# Hack_Final.net
KiCad netlist of a schematic drawn in Altium Designer
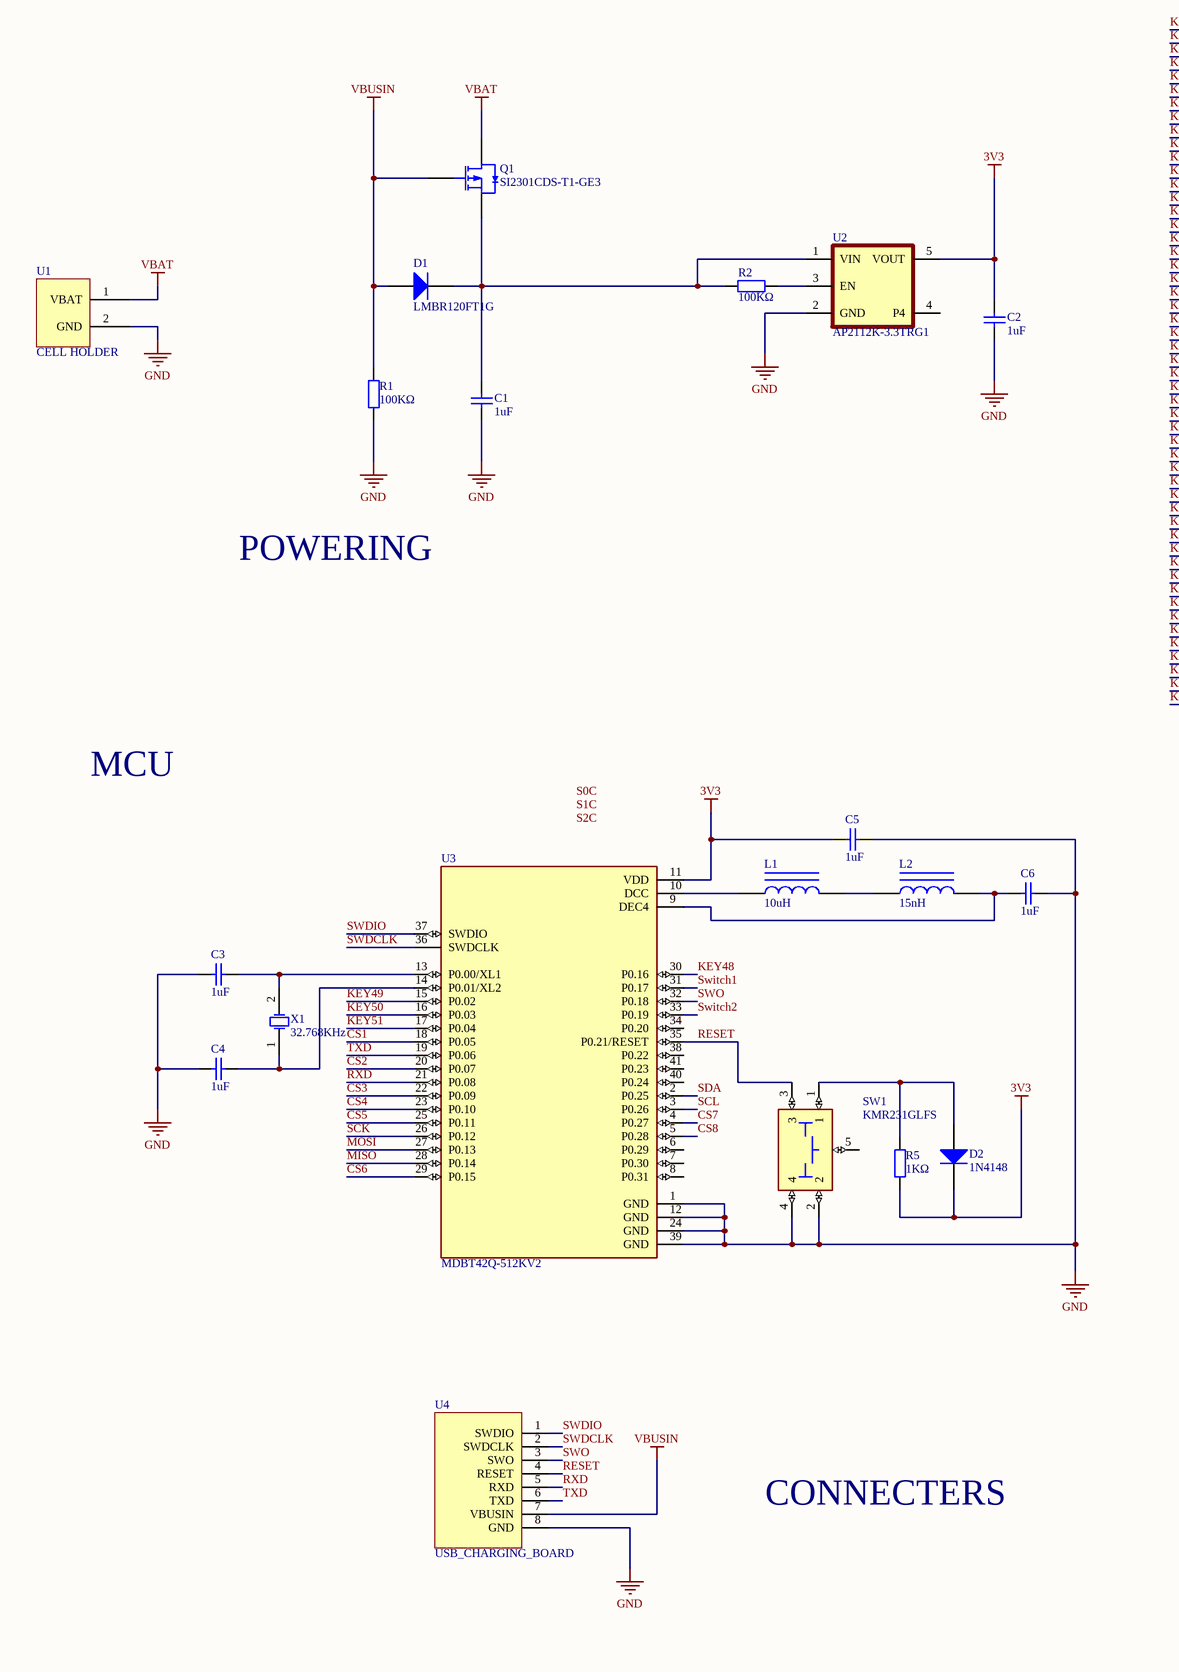
[diagram p0: Hack_Final.SchDoc, left]
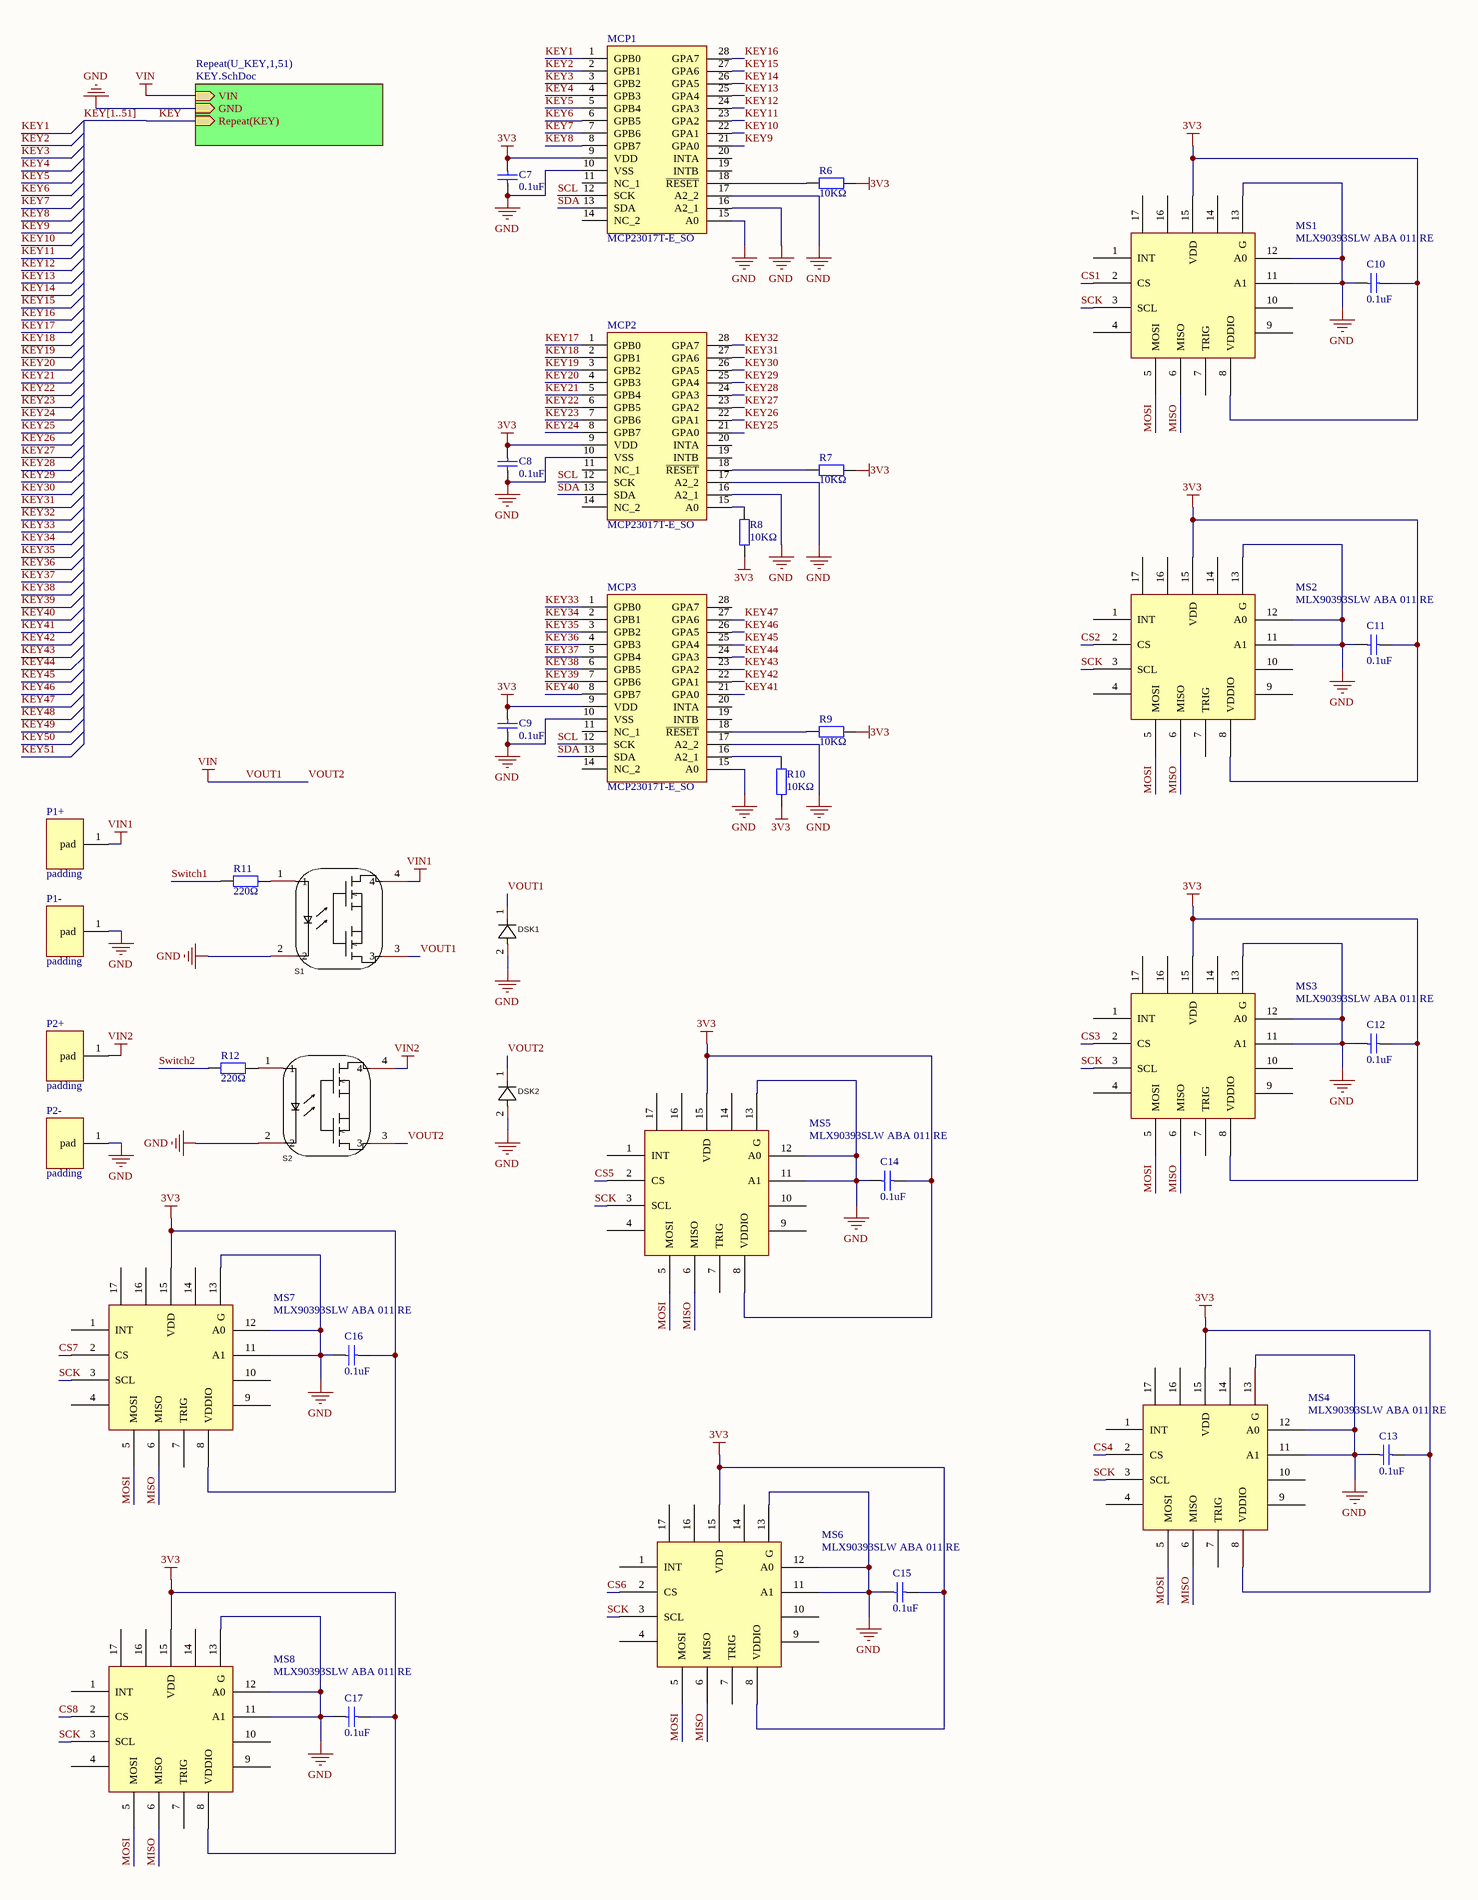
[diagram p1: Hack_Final.SchDoc, right]

(export (version "E")
  (design (tool "Eeschema 10.0.6"))
  (components
    (comp (ref "C1")
      (value "1uF")
      (footprint "0603_C")
      (description "capacitance")
      (libsource (lib "Hack_V6") (part "CAP"))
    )
    (comp (ref "C2")
      (value "1uF")
      (footprint "0603_C")
      (description "capacitance")
      (libsource (lib "Hack_V6") (part "CAP"))
    )
    (comp (ref "C3")
      (value "1uF")
      (footprint "0603_C")
      (description "capacitance")
      (libsource (lib "Hack_V6") (part "CAP"))
    )
    (comp (ref "C4")
      (value "1uF")
      (footprint "0603_C")
      (description "capacitance")
      (libsource (lib "Hack_V6") (part "CAP"))
    )
    (comp (ref "C5")
      (value "1uF")
      (footprint "0603_C")
      (description "capacitance")
      (libsource (lib "Hack_V6") (part "CAP"))
    )
    (comp (ref "C6")
      (value "1uF")
      (footprint "0603_C")
      (description "capacitance")
      (libsource (lib "Hack_V6") (part "CAP"))
    )
    (comp (ref "C7")
      (value "0.1uF")
      (footprint "0603_C")
      (description "capacitance")
      (libsource (lib "Hack_V6") (part "CAP"))
    )
    (comp (ref "C8")
      (value "0.1uF")
      (footprint "0603_C")
      (description "capacitance")
      (libsource (lib "Hack_V6") (part "CAP"))
    )
    (comp (ref "C9")
      (value "0.1uF")
      (footprint "0603_C")
      (description "capacitance")
      (libsource (lib "Hack_V6") (part "CAP"))
    )
    (comp (ref "C10")
      (value "0.1uF")
      (footprint "0603_C")
      (description "capacitance")
      (libsource (lib "Hack_V6") (part "CAP"))
    )
    (comp (ref "C11")
      (value "0.1uF")
      (footprint "0603_C")
      (description "capacitance")
      (libsource (lib "Hack_V6") (part "CAP"))
    )
    (comp (ref "C12")
      (value "0.1uF")
      (footprint "0603_C")
      (description "capacitance")
      (libsource (lib "Hack_V6") (part "CAP"))
    )
    (comp (ref "C13")
      (value "0.1uF")
      (footprint "0603_C")
      (description "capacitance")
      (libsource (lib "Hack_V6") (part "CAP"))
    )
    (comp (ref "C14")
      (value "0.1uF")
      (footprint "0603_C")
      (description "capacitance")
      (libsource (lib "Hack_V6") (part "CAP"))
    )
    (comp (ref "C15")
      (value "0.1uF")
      (footprint "0603_C")
      (description "capacitance")
      (libsource (lib "Hack_V6") (part "CAP"))
    )
    (comp (ref "C16")
      (value "0.1uF")
      (footprint "0603_C")
      (description "capacitance")
      (libsource (lib "Hack_V6") (part "CAP"))
    )
    (comp (ref "C17")
      (value "0.1uF")
      (footprint "0603_C")
      (description "capacitance")
      (libsource (lib "Hack_V6") (part "CAP"))
    )
    (comp (ref "D1")
      (value "LMBR120FT1G")
      (footprint "SOD-123")
      (description "schottky diode")
      (libsource (lib "Hack_V6") (part "DIO_5"))
    )
    (comp (ref "D2")
      (value "1N4148")
      (footprint "SOD-323F")
      (description "diode")
      (libsource (lib "MAGNETO") (part "DIO_4"))
    )
    (comp (ref "DSK1")
      (value "DSK16")
      (footprint "DSK16")
      (fields (field (name "MANUFACTURER") "HXY MOSFET(华轩阳电子)"))
      (libsource (lib "Hack_V4") (part "DSK16"))
    )
    (comp (ref "DSK2")
      (value "DSK16")
      (footprint "DSK16")
      (fields (field (name "MANUFACTURER") "HXY MOSFET(华轩阳电子)"))
      (libsource (lib "Hack_V4") (part "DSK16"))
    )
    (comp (ref "L1")
      (value "10uH")
      (footprint "0402_L")
      (description "inductance")
      (libsource (lib "magjoint_MCU") (part "IND_10uH"))
    )
    (comp (ref "L2")
      (value "15nH")
      (footprint "0402_L")
      (description "inductance")
      (libsource (lib "magjoint_MCU") (part "IND_15nH"))
    )
    (comp (ref "MCP1")
      (value "MCP23017T-E_SO")
      (footprint "SamacSys:SOIC127P1030X265-28N")
      (description "Integrated Circuit")
      (fields
        (field (name "MANUFACTURER_PART_NUMBER") "MCP23017T-E/SO")
        (field (name "MOUSER PART NUMBER") "579-MCP23017T-E/SO")
      )
      (libsource (lib "*") (part "MCP23017T-E_SO"))
    )
    (comp (ref "MCP2")
      (value "MCP23017T-E_SO")
      (footprint "SamacSys:SOIC127P1030X265-28N")
      (description "Integrated Circuit")
      (fields
        (field (name "MANUFACTURER_PART_NUMBER") "MCP23017T-E/SO")
        (field (name "MOUSER PART NUMBER") "579-MCP23017T-E/SO")
      )
      (libsource (lib "*") (part "MCP23017T-E_SO"))
    )
    (comp (ref "MCP3")
      (value "MCP23017T-E_SO")
      (footprint "SamacSys:SOIC127P1030X265-28N")
      (description "Integrated Circuit")
      (fields
        (field (name "MANUFACTURER_PART_NUMBER") "MCP23017T-E/SO")
        (field (name "MOUSER PART NUMBER") "579-MCP23017T-E/SO")
      )
      (libsource (lib "*") (part "MCP23017T-E_SO"))
    )
    (comp (ref "MS1")
      (value "MLX90393SLW ABA 011 RE")
      (footprint "VQFN-16_EP_3.0x3.0xo.5P")
      (description "sensor")
      (libsource (lib "magjoint_MCU") (part "MLX90393SLW ABA 011 RE"))
    )
    (comp (ref "MS2")
      (value "MLX90393SLW ABA 011 RE")
      (footprint "VQFN-16_EP_3.0x3.0xo.5P")
      (description "sensor")
      (libsource (lib "magjoint_MCU") (part "MLX90393SLW ABA 011 RE"))
    )
    (comp (ref "MS3")
      (value "MLX90393SLW ABA 011 RE")
      (footprint "VQFN-16_EP_3.0x3.0xo.5P")
      (description "sensor")
      (libsource (lib "magjoint_MCU") (part "MLX90393SLW ABA 011 RE"))
    )
    (comp (ref "MS4")
      (value "MLX90393SLW ABA 011 RE")
      (footprint "VQFN-16_EP_3.0x3.0xo.5P")
      (description "sensor")
      (libsource (lib "magjoint_MCU") (part "MLX90393SLW ABA 011 RE"))
    )
    (comp (ref "MS5")
      (value "MLX90393SLW ABA 011 RE")
      (footprint "VQFN-16_EP_3.0x3.0xo.5P")
      (description "sensor")
      (libsource (lib "magjoint_MCU") (part "MLX90393SLW ABA 011 RE"))
    )
    (comp (ref "MS6")
      (value "MLX90393SLW ABA 011 RE")
      (footprint "VQFN-16_EP_3.0x3.0xo.5P")
      (description "sensor")
      (libsource (lib "magjoint_MCU") (part "MLX90393SLW ABA 011 RE"))
    )
    (comp (ref "MS7")
      (value "MLX90393SLW ABA 011 RE")
      (footprint "VQFN-16_EP_3.0x3.0xo.5P")
      (description "sensor")
      (libsource (lib "magjoint_MCU") (part "MLX90393SLW ABA 011 RE"))
    )
    (comp (ref "MS8")
      (value "MLX90393SLW ABA 011 RE")
      (footprint "VQFN-16_EP_3.0x3.0xo.5P")
      (description "sensor")
      (libsource (lib "magjoint_MCU") (part "MLX90393SLW ABA 011 RE"))
    )
    (comp (ref "P1+") (value "padding") (footprint "PADDING2") (libsource (lib "Hack_V4") (part "padding2")))
    (comp (ref "P1-") (value "padding") (footprint "PADDING2") (libsource (lib "Hack_V4") (part "padding2")))
    (comp (ref "P2+") (value "padding") (footprint "PADDING2") (libsource (lib "Hack_V4") (part "padding2")))
    (comp (ref "P2-") (value "padding") (footprint "PADDING2") (libsource (lib "Hack_V4") (part "padding2")))
    (comp (ref "Q1")
      (value "SI2301CDS-T1-GE3")
      (footprint "SOT-23(SOT-23-3)")
      (description "field effect tube")
      (libsource (lib "magjoint_MCU") (part "MOS"))
    )
    (comp (ref "R1")
      (value "100KΩ")
      (footprint "0603_R")
      (description "resistance")
      (libsource (lib "") (part "RES_3"))
    )
    (comp (ref "R2")
      (value "100KΩ")
      (footprint "0603_R")
      (description "resistance")
      (libsource (lib "Hack_V6") (part "RES"))
    )
    (comp (ref "R5")
      (value "1KΩ")
      (footprint "0603_R")
      (description "resistance")
      (libsource (lib "") (part "RES_2"))
    )
    (comp (ref "R6")
      (value "10KΩ")
      (footprint "0603_R")
      (description "resistance")
      (libsource (lib "Hack_V6") (part "RES"))
    )
    (comp (ref "R7")
      (value "10KΩ")
      (footprint "0603_R")
      (description "resistance")
      (libsource (lib "Hack_V6") (part "RES"))
    )
    (comp (ref "R8")
      (value "10KΩ")
      (footprint "0603_R")
      (description "resistance")
      (libsource (lib "") (part "RES_2"))
    )
    (comp (ref "R9")
      (value "10KΩ")
      (footprint "0603_R")
      (description "resistance")
      (libsource (lib "Hack_V6") (part "RES"))
    )
    (comp (ref "R10")
      (value "10KΩ")
      (footprint "0603_R")
      (description "resistance")
      (libsource (lib "") (part "RES_2"))
    )
    (comp (ref "R11")
      (value "220Ω")
      (footprint "0603_R")
      (description "resistance")
      (libsource (lib "") (part "RES_1"))
    )
    (comp (ref "R12")
      (value "220Ω")
      (footprint "0603_R")
      (description "resistance")
      (libsource (lib "") (part "RES_1"))
    )
    (comp (ref "S1")
      (value "GAQY212GSX")
      (footprint "SOP-4_L4.3-W4.4-P2.54-LS6.8-TR")
      (fields (field (name "MANUFACTURER") "SUPSiC(国晶微半导体)"))
      (libsource (lib "Hack_V3") (part "GAQY212GSX"))
    )
    (comp (ref "S2")
      (value "GAQY212GSX")
      (footprint "SOP-4_L4.3-W4.4-P2.54-LS6.8-TR")
      (fields (field (name "MANUFACTURER") "SUPSiC(国晶微半导体)"))
      (libsource (lib "Hack_V3") (part "GAQY212GSX"))
    )
    (comp (ref "SW1")
      (value "KMR231GLFS")
      (footprint "KMR231GLFS")
      (description "Tactile Switch SPST-NO Top Actuated Surface Mount")
      (libsource (lib "magjoint_MCU") (part "KMR231GLFS"))
    )
    (comp (ref "U1")
      (value "CELL HOLDER")
      (footprint "BAT_MX 1.25-WI-2P")
      (description "button cell battary holder BS-08-B2AA025")
      (libsource (lib "magjoint_MCU") (part "BAT"))
    )
    (comp (ref "U2")
      (value "AP2112K-3.3TRG1")
      (footprint "SOT95P285X140-5N")
      (description "LDO_ low dropout linear regulator")
      (libsource (lib "magjoint_MCU") (part "AP2112K"))
    )
    (comp (ref "U3")
      (value "MDBT42Q-512KV2")
      (footprint "SMD_10.0X16.0")
      (libsource (lib "magjoint_MCU") (part "MDBT42Q-512KV2"))
    )
    (comp (ref "U4")
      (value "USB_CHARGING_BOARD")
      (footprint "FPC0.5 2H-WS-8P")
      (libsource (lib "magjoint_MCU") (part "USB_CHARGING_BOARD"))
    )
    (comp (ref "X1")
      (value "32.768KHz")
      (footprint "SMD-3215_2P FC - 135")
      (description "crystal")
      (libsource (lib "magjoint_MCU") (part "ABS07-32.768KHZ-7-T"))
    )
  )
  (nets
    (net (code "1") (name "/CS1") (class "Default")
      (node (ref "MS1") (pin "2") (pinfunction "CS_2") (pintype "passive"))
      (node (ref "U3") (pin "18") (pinfunction "P0.05_18") (pintype "bidirectional"))
    )
    (net (code "2") (name "/CS2") (class "Default")
      (node (ref "MS2") (pin "2") (pinfunction "CS_2") (pintype "passive"))
      (node (ref "U3") (pin "20") (pinfunction "P0.07_20") (pintype "bidirectional"))
    )
    (net (code "3") (name "/CS3") (class "Default")
      (node (ref "MS3") (pin "2") (pinfunction "CS_2") (pintype "passive"))
      (node (ref "U3") (pin "22") (pinfunction "P0.09_22") (pintype "bidirectional"))
    )
    (net (code "4") (name "/CS4") (class "Default")
      (node (ref "MS4") (pin "2") (pinfunction "CS_2") (pintype "passive"))
      (node (ref "U3") (pin "23") (pinfunction "P0.10_23") (pintype "bidirectional"))
    )
    (net (code "5") (name "/CS5") (class "Default")
      (node (ref "MS5") (pin "2") (pinfunction "CS_2") (pintype "passive"))
      (node (ref "U3") (pin "25") (pinfunction "P0.11_25") (pintype "bidirectional"))
    )
    (net (code "6") (name "/CS6") (class "Default")
      (node (ref "MS6") (pin "2") (pinfunction "CS_2") (pintype "passive"))
      (node (ref "U3") (pin "29") (pinfunction "P0.15_29") (pintype "bidirectional"))
    )
    (net (code "7") (name "/CS7") (class "Default")
      (node (ref "MS7") (pin "2") (pinfunction "CS_2") (pintype "passive"))
      (node (ref "U3") (pin "4") (pinfunction "P0.27_4") (pintype "bidirectional"))
    )
    (net (code "8") (name "/CS8") (class "Default")
      (node (ref "MS8") (pin "2") (pinfunction "CS_2") (pintype "passive"))
      (node (ref "U3") (pin "5") (pinfunction "P0.28_5") (pintype "bidirectional"))
    )
    (net (code "10") (name "/KEY1") (class "Default")
      (node (ref "MCP1") (pin "1") (pinfunction "GPB0_1") (pintype "passive"))
    )
    (net (code "11") (name "/KEY2") (class "Default")
      (node (ref "MCP1") (pin "2") (pinfunction "GPB1_2") (pintype "passive"))
    )
    (net (code "12") (name "/KEY3") (class "Default")
      (node (ref "MCP1") (pin "3") (pinfunction "GPB2_3") (pintype "passive"))
    )
    (net (code "13") (name "/KEY4") (class "Default")
      (node (ref "MCP1") (pin "4") (pinfunction "GPB3_4") (pintype "passive"))
    )
    (net (code "14") (name "/KEY5") (class "Default")
      (node (ref "MCP1") (pin "5") (pinfunction "GPB4_5") (pintype "passive"))
    )
    (net (code "15") (name "/KEY6") (class "Default")
      (node (ref "MCP1") (pin "6") (pinfunction "GPB5_6") (pintype "passive"))
    )
    (net (code "16") (name "/KEY7") (class "Default")
      (node (ref "MCP1") (pin "7") (pinfunction "GPB6_7") (pintype "passive"))
    )
    (net (code "17") (name "/KEY8") (class "Default")
      (node (ref "MCP1") (pin "8") (pinfunction "GPB7_8") (pintype "passive"))
    )
    (net (code "18") (name "/KEY9") (class "Default")
      (node (ref "MCP1") (pin "21") (pinfunction "GPA0_21") (pintype "passive"))
    )
    (net (code "19") (name "/KEY10") (class "Default")
      (node (ref "MCP1") (pin "22") (pinfunction "GPA1_22") (pintype "passive"))
    )
    (net (code "20") (name "/KEY11") (class "Default")
      (node (ref "MCP1") (pin "23") (pinfunction "GPA2_23") (pintype "passive"))
    )
    (net (code "21") (name "/KEY12") (class "Default")
      (node (ref "MCP1") (pin "24") (pinfunction "GPA3_24") (pintype "passive"))
    )
    (net (code "22") (name "/KEY13") (class "Default")
      (node (ref "MCP1") (pin "25") (pinfunction "GPA4_25") (pintype "passive"))
    )
    (net (code "23") (name "/KEY14") (class "Default")
      (node (ref "MCP1") (pin "26") (pinfunction "GPA5_26") (pintype "passive"))
    )
    (net (code "24") (name "/KEY15") (class "Default")
      (node (ref "MCP1") (pin "27") (pinfunction "GPA6_27") (pintype "passive"))
    )
    (net (code "25") (name "/KEY16") (class "Default")
      (node (ref "MCP1") (pin "28") (pinfunction "GPA7_28") (pintype "passive"))
    )
    (net (code "26") (name "/KEY17") (class "Default")
      (node (ref "MCP2") (pin "1") (pinfunction "GPB0_1") (pintype "passive"))
    )
    (net (code "27") (name "/KEY18") (class "Default")
      (node (ref "MCP2") (pin "2") (pinfunction "GPB1_2") (pintype "passive"))
    )
    (net (code "28") (name "/KEY19") (class "Default")
      (node (ref "MCP2") (pin "3") (pinfunction "GPB2_3") (pintype "passive"))
    )
    (net (code "29") (name "/KEY20") (class "Default")
      (node (ref "MCP2") (pin "4") (pinfunction "GPB3_4") (pintype "passive"))
    )
    (net (code "30") (name "/KEY21") (class "Default")
      (node (ref "MCP2") (pin "5") (pinfunction "GPB4_5") (pintype "passive"))
    )
    (net (code "31") (name "/KEY22") (class "Default")
      (node (ref "MCP2") (pin "6") (pinfunction "GPB5_6") (pintype "passive"))
    )
    (net (code "32") (name "/KEY23") (class "Default")
      (node (ref "MCP2") (pin "7") (pinfunction "GPB6_7") (pintype "passive"))
    )
    (net (code "33") (name "/KEY24") (class "Default")
      (node (ref "MCP2") (pin "8") (pinfunction "GPB7_8") (pintype "passive"))
    )
    (net (code "34") (name "/KEY25") (class "Default")
      (node (ref "MCP2") (pin "21") (pinfunction "GPA0_21") (pintype "passive"))
    )
    (net (code "35") (name "/KEY26") (class "Default")
      (node (ref "MCP2") (pin "22") (pinfunction "GPA1_22") (pintype "passive"))
    )
    (net (code "36") (name "/KEY27") (class "Default")
      (node (ref "MCP2") (pin "23") (pinfunction "GPA2_23") (pintype "passive"))
    )
    (net (code "37") (name "/KEY28") (class "Default")
      (node (ref "MCP2") (pin "24") (pinfunction "GPA3_24") (pintype "passive"))
    )
    (net (code "38") (name "/KEY29") (class "Default")
      (node (ref "MCP2") (pin "25") (pinfunction "GPA4_25") (pintype "passive"))
    )
    (net (code "39") (name "/KEY30") (class "Default")
      (node (ref "MCP2") (pin "26") (pinfunction "GPA5_26") (pintype "passive"))
    )
    (net (code "40") (name "/KEY31") (class "Default")
      (node (ref "MCP2") (pin "27") (pinfunction "GPA6_27") (pintype "passive"))
    )
    (net (code "41") (name "/KEY32") (class "Default")
      (node (ref "MCP2") (pin "28") (pinfunction "GPA7_28") (pintype "passive"))
    )
    (net (code "42") (name "/KEY33") (class "Default")
      (node (ref "MCP3") (pin "1") (pinfunction "GPB0_1") (pintype "passive"))
    )
    (net (code "43") (name "/KEY34") (class "Default")
      (node (ref "MCP3") (pin "2") (pinfunction "GPB1_2") (pintype "passive"))
    )
    (net (code "44") (name "/KEY35") (class "Default")
      (node (ref "MCP3") (pin "3") (pinfunction "GPB2_3") (pintype "passive"))
    )
    (net (code "45") (name "/KEY36") (class "Default")
      (node (ref "MCP3") (pin "4") (pinfunction "GPB3_4") (pintype "passive"))
    )
    (net (code "46") (name "/KEY37") (class "Default")
      (node (ref "MCP3") (pin "5") (pinfunction "GPB4_5") (pintype "passive"))
    )
    (net (code "47") (name "/KEY38") (class "Default")
      (node (ref "MCP3") (pin "6") (pinfunction "GPB5_6") (pintype "passive"))
    )
    (net (code "48") (name "/KEY39") (class "Default")
      (node (ref "MCP3") (pin "7") (pinfunction "GPB6_7") (pintype "passive"))
    )
    (net (code "49") (name "/KEY40") (class "Default")
      (node (ref "MCP3") (pin "8") (pinfunction "GPB7_8") (pintype "passive"))
    )
    (net (code "50") (name "/KEY41") (class "Default")
      (node (ref "MCP3") (pin "21") (pinfunction "GPA0_21") (pintype "passive"))
    )
    (net (code "51") (name "/KEY42") (class "Default")
      (node (ref "MCP3") (pin "22") (pinfunction "GPA1_22") (pintype "passive"))
    )
    (net (code "52") (name "/KEY43") (class "Default")
      (node (ref "MCP3") (pin "23") (pinfunction "GPA2_23") (pintype "passive"))
    )
    (net (code "53") (name "/KEY44") (class "Default")
      (node (ref "MCP3") (pin "24") (pinfunction "GPA3_24") (pintype "passive"))
    )
    (net (code "54") (name "/KEY45") (class "Default")
      (node (ref "MCP3") (pin "25") (pinfunction "GPA4_25") (pintype "passive"))
    )
    (net (code "55") (name "/KEY46") (class "Default")
      (node (ref "MCP3") (pin "26") (pinfunction "GPA5_26") (pintype "passive"))
    )
    (net (code "56") (name "/KEY47") (class "Default")
      (node (ref "MCP3") (pin "27") (pinfunction "GPA6_27") (pintype "passive"))
    )
    (net (code "57") (name "/KEY48") (class "Default")
      (node (ref "U3") (pin "30") (pinfunction "P0.16_30") (pintype "bidirectional"))
    )
    (net (code "58") (name "/KEY49") (class "Default")
      (node (ref "U3") (pin "15") (pinfunction "P0.02_15") (pintype "bidirectional"))
    )
    (net (code "59") (name "/KEY50") (class "Default")
      (node (ref "U3") (pin "16") (pinfunction "P0.03_16") (pintype "bidirectional"))
    )
    (net (code "60") (name "/KEY51") (class "Default")
      (node (ref "U3") (pin "17") (pinfunction "P0.04_17") (pintype "bidirectional"))
    )
    (net (code "62") (name "/MISO") (class "Default")
      (node (ref "MS1") (pin "6") (pinfunction "MISO_6") (pintype "passive"))
      (node (ref "MS2") (pin "6") (pinfunction "MISO_6") (pintype "passive"))
      (node (ref "MS3") (pin "6") (pinfunction "MISO_6") (pintype "passive"))
      (node (ref "MS4") (pin "6") (pinfunction "MISO_6") (pintype "passive"))
      (node (ref "MS5") (pin "6") (pinfunction "MISO_6") (pintype "passive"))
      (node (ref "MS6") (pin "6") (pinfunction "MISO_6") (pintype "passive"))
      (node (ref "MS7") (pin "6") (pinfunction "MISO_6") (pintype "passive"))
      (node (ref "MS8") (pin "6") (pinfunction "MISO_6") (pintype "passive"))
      (node (ref "U3") (pin "28") (pinfunction "P0.14_28") (pintype "bidirectional"))
    )
    (net (code "63") (name "/MOSI") (class "Default")
      (node (ref "MS1") (pin "5") (pinfunction "MOSI_5") (pintype "passive"))
      (node (ref "MS2") (pin "5") (pinfunction "MOSI_5") (pintype "passive"))
      (node (ref "MS3") (pin "5") (pinfunction "MOSI_5") (pintype "passive"))
      (node (ref "MS4") (pin "5") (pinfunction "MOSI_5") (pintype "passive"))
      (node (ref "MS5") (pin "5") (pinfunction "MOSI_5") (pintype "passive"))
      (node (ref "MS6") (pin "5") (pinfunction "MOSI_5") (pintype "passive"))
      (node (ref "MS7") (pin "5") (pinfunction "MOSI_5") (pintype "passive"))
      (node (ref "MS8") (pin "5") (pinfunction "MOSI_5") (pintype "passive"))
      (node (ref "U3") (pin "27") (pinfunction "P0.13_27") (pintype "bidirectional"))
    )
    (net (code "64") (name "/RESET") (class "Default")
      (node (ref "SW1") (pin "3") (pinfunction "3_3") (pintype "bidirectional"))
      (node (ref "U3") (pin "35") (pinfunction "P0.21/RESET_35") (pintype "bidirectional"))
      (node (ref "U4") (pin "4") (pinfunction "RESET_4") (pintype "passive"))
    )
    (net (code "65") (name "/RXD") (class "Default")
      (node (ref "U3") (pin "21") (pinfunction "P0.08_21") (pintype "bidirectional"))
      (node (ref "U4") (pin "5") (pinfunction "RXD_5") (pintype "passive"))
    )
    (net (code "69") (name "/SCK") (class "Default")
      (node (ref "MS1") (pin "3") (pinfunction "SCL_3") (pintype "passive"))
      (node (ref "MS2") (pin "3") (pinfunction "SCL_3") (pintype "passive"))
      (node (ref "MS3") (pin "3") (pinfunction "SCL_3") (pintype "passive"))
      (node (ref "MS4") (pin "3") (pinfunction "SCL_3") (pintype "passive"))
      (node (ref "MS5") (pin "3") (pinfunction "SCL_3") (pintype "passive"))
      (node (ref "MS6") (pin "3") (pinfunction "SCL_3") (pintype "passive"))
      (node (ref "MS7") (pin "3") (pinfunction "SCL_3") (pintype "passive"))
      (node (ref "MS8") (pin "3") (pinfunction "SCL_3") (pintype "passive"))
      (node (ref "U3") (pin "26") (pinfunction "P0.12_26") (pintype "bidirectional"))
    )
    (net (code "70") (name "/SCL") (class "Default")
      (node (ref "MCP1") (pin "12") (pinfunction "SCK_12") (pintype "passive"))
      (node (ref "MCP2") (pin "12") (pinfunction "SCK_12") (pintype "passive"))
      (node (ref "MCP3") (pin "12") (pinfunction "SCK_12") (pintype "passive"))
      (node (ref "U3") (pin "3") (pinfunction "P0.26_3") (pintype "bidirectional"))
    )
    (net (code "71") (name "/SDA") (class "Default")
      (node (ref "MCP1") (pin "13") (pinfunction "SDA_13") (pintype "passive"))
      (node (ref "MCP2") (pin "13") (pinfunction "SDA_13") (pintype "passive"))
      (node (ref "MCP3") (pin "13") (pinfunction "SDA_13") (pintype "passive"))
      (node (ref "U3") (pin "2") (pinfunction "P0.25_2") (pintype "bidirectional"))
    )
    (net (code "72") (name "/SWDCLK") (class "Default")
      (node (ref "U3") (pin "36") (pinfunction "SWDCLK_36") (pintype "power_in"))
      (node (ref "U4") (pin "2") (pinfunction "SWDCLK_2") (pintype "passive"))
    )
    (net (code "73") (name "/SWDIO") (class "Default")
      (node (ref "U3") (pin "37") (pinfunction "SWDIO_37") (pintype "bidirectional"))
      (node (ref "U4") (pin "1") (pinfunction "SWDIO_1") (pintype "passive"))
    )
    (net (code "74") (name "/SWO") (class "Default")
      (node (ref "U3") (pin "32") (pinfunction "P0.18_32") (pintype "bidirectional"))
      (node (ref "U4") (pin "3") (pinfunction "SWO_3") (pintype "passive"))
    )
    (net (code "75") (name "/Switch1") (class "Default")
      (node (ref "R11") (pin "1") (pinfunction "1_1") (pintype "passive"))
      (node (ref "U3") (pin "31") (pinfunction "P0.17_31") (pintype "bidirectional"))
    )
    (net (code "76") (name "/Switch2") (class "Default")
      (node (ref "R12") (pin "1") (pinfunction "1_1") (pintype "passive"))
      (node (ref "U3") (pin "33") (pinfunction "P0.19_33") (pintype "bidirectional"))
    )
    (net (code "77") (name "/TXD") (class "Default")
      (node (ref "U3") (pin "19") (pinfunction "P0.06_19") (pintype "bidirectional"))
      (node (ref "U4") (pin "6") (pinfunction "TXD_6") (pintype "passive"))
    )
    (net (code "78") (name "3V3") (class "Default")
      (node (ref "C10") (pin "2") (pinfunction "2_2") (pintype "passive"))
      (node (ref "C11") (pin "2") (pinfunction "2_2") (pintype "passive"))
      (node (ref "C12") (pin "2") (pinfunction "2_2") (pintype "passive"))
      (node (ref "C13") (pin "2") (pinfunction "2_2") (pintype "passive"))
      (node (ref "C14") (pin "2") (pinfunction "2_2") (pintype "passive"))
      (node (ref "C15") (pin "2") (pinfunction "2_2") (pintype "passive"))
      (node (ref "C16") (pin "2") (pinfunction "2_2") (pintype "passive"))
      (node (ref "C17") (pin "2") (pinfunction "2_2") (pintype "passive"))
      (node (ref "C2") (pin "2") (pinfunction "2_2") (pintype "passive"))
      (node (ref "C5") (pin "2") (pinfunction "2_2") (pintype "passive"))
      (node (ref "C7") (pin "1") (pinfunction "1_1") (pintype "passive"))
      (node (ref "C8") (pin "1") (pinfunction "1_1") (pintype "passive"))
      (node (ref "C9") (pin "1") (pinfunction "1_1") (pintype "passive"))
      (node (ref "D2") (pin "2") (pinfunction "K_2") (pintype "passive"))
      (node (ref "MCP1") (pin "9") (pinfunction "VDD_9") (pintype "passive"))
      (node (ref "MCP2") (pin "9") (pinfunction "VDD_9") (pintype "passive"))
      (node (ref "MCP3") (pin "9") (pinfunction "VDD_9") (pintype "passive"))
      (node (ref "MS1") (pin "15") (pinfunction "VDD_15") (pintype "passive"))
      (node (ref "MS1") (pin "8") (pinfunction "VDDIO_8") (pintype "passive"))
      (node (ref "MS2") (pin "15") (pinfunction "VDD_15") (pintype "passive"))
      (node (ref "MS2") (pin "8") (pinfunction "VDDIO_8") (pintype "passive"))
      (node (ref "MS3") (pin "15") (pinfunction "VDD_15") (pintype "passive"))
      (node (ref "MS3") (pin "8") (pinfunction "VDDIO_8") (pintype "passive"))
      (node (ref "MS4") (pin "15") (pinfunction "VDD_15") (pintype "passive"))
      (node (ref "MS4") (pin "8") (pinfunction "VDDIO_8") (pintype "passive"))
      (node (ref "MS5") (pin "15") (pinfunction "VDD_15") (pintype "passive"))
      (node (ref "MS5") (pin "8") (pinfunction "VDDIO_8") (pintype "passive"))
      (node (ref "MS6") (pin "15") (pinfunction "VDD_15") (pintype "passive"))
      (node (ref "MS6") (pin "8") (pinfunction "VDDIO_8") (pintype "passive"))
      (node (ref "MS7") (pin "15") (pinfunction "VDD_15") (pintype "passive"))
      (node (ref "MS7") (pin "8") (pinfunction "VDDIO_8") (pintype "passive"))
      (node (ref "MS8") (pin "15") (pinfunction "VDD_15") (pintype "passive"))
      (node (ref "MS8") (pin "8") (pinfunction "VDDIO_8") (pintype "passive"))
      (node (ref "R10") (pin "2") (pinfunction "2_2") (pintype "passive"))
      (node (ref "R5") (pin "2") (pinfunction "2_2") (pintype "passive"))
      (node (ref "R6") (pin "1") (pinfunction "1_1") (pintype "passive"))
      (node (ref "R7") (pin "1") (pinfunction "1_1") (pintype "passive"))
      (node (ref "R8") (pin "2") (pinfunction "2_2") (pintype "passive"))
      (node (ref "R9") (pin "1") (pinfunction "1_1") (pintype "passive"))
      (node (ref "U2") (pin "5") (pinfunction "VOUT_5") (pintype "power_in"))
      (node (ref "U3") (pin "11") (pinfunction "VDD_11") (pintype "power_in"))
    )
    (net (code "79") (name "GND") (class "Default")
      (node (ref "C1") (pin "1") (pinfunction "1_1") (pintype "passive"))
      (node (ref "C10") (pin "1") (pinfunction "1_1") (pintype "passive"))
      (node (ref "C11") (pin "1") (pinfunction "1_1") (pintype "passive"))
      (node (ref "C12") (pin "1") (pinfunction "1_1") (pintype "passive"))
      (node (ref "C13") (pin "1") (pinfunction "1_1") (pintype "passive"))
      (node (ref "C14") (pin "1") (pinfunction "1_1") (pintype "passive"))
      (node (ref "C15") (pin "1") (pinfunction "1_1") (pintype "passive"))
      (node (ref "C16") (pin "1") (pinfunction "1_1") (pintype "passive"))
      (node (ref "C17") (pin "1") (pinfunction "1_1") (pintype "passive"))
      (node (ref "C2") (pin "1") (pinfunction "1_1") (pintype "passive"))
      (node (ref "C3") (pin "2") (pinfunction "2_2") (pintype "passive"))
      (node (ref "C4") (pin "2") (pinfunction "2_2") (pintype "passive"))
      (node (ref "C5") (pin "1") (pinfunction "1_1") (pintype "passive"))
      (node (ref "C6") (pin "1") (pinfunction "1_1") (pintype "passive"))
      (node (ref "C7") (pin "2") (pinfunction "2_2") (pintype "passive"))
      (node (ref "C8") (pin "2") (pinfunction "2_2") (pintype "passive"))
      (node (ref "C9") (pin "2") (pinfunction "2_2") (pintype "passive"))
      (node (ref "DSK1") (pin "2") (pinfunction "A_2") (pintype "passive"))
      (node (ref "DSK2") (pin "2") (pinfunction "A_2") (pintype "passive"))
      (node (ref "MCP1") (pin "10") (pinfunction "VSS_10") (pintype "passive"))
      (node (ref "MCP1") (pin "15") (pinfunction "A0_15") (pintype "passive"))
      (node (ref "MCP1") (pin "16") (pinfunction "A2_1_16") (pintype "passive"))
      (node (ref "MCP1") (pin "17") (pinfunction "A2_2_17") (pintype "passive"))
      (node (ref "MCP2") (pin "10") (pinfunction "VSS_10") (pintype "passive"))
      (node (ref "MCP2") (pin "16") (pinfunction "A2_1_16") (pintype "passive"))
      (node (ref "MCP2") (pin "17") (pinfunction "A2_2_17") (pintype "passive"))
      (node (ref "MCP3") (pin "10") (pinfunction "VSS_10") (pintype "passive"))
      (node (ref "MCP3") (pin "15") (pinfunction "A0_15") (pintype "passive"))
      (node (ref "MCP3") (pin "17") (pinfunction "A2_2_17") (pintype "passive"))
      (node (ref "MS1") (pin "11") (pinfunction "A1_11") (pintype "passive"))
      (node (ref "MS1") (pin "12") (pinfunction "A0_12") (pintype "passive"))
      (node (ref "MS1") (pin "13") (pinfunction "G_13") (pintype "passive"))
      (node (ref "MS2") (pin "11") (pinfunction "A1_11") (pintype "passive"))
      (node (ref "MS2") (pin "12") (pinfunction "A0_12") (pintype "passive"))
      (node (ref "MS2") (pin "13") (pinfunction "G_13") (pintype "passive"))
      (node (ref "MS3") (pin "11") (pinfunction "A1_11") (pintype "passive"))
      (node (ref "MS3") (pin "12") (pinfunction "A0_12") (pintype "passive"))
      (node (ref "MS3") (pin "13") (pinfunction "G_13") (pintype "passive"))
      (node (ref "MS4") (pin "11") (pinfunction "A1_11") (pintype "passive"))
      (node (ref "MS4") (pin "12") (pinfunction "A0_12") (pintype "passive"))
      (node (ref "MS4") (pin "13") (pinfunction "G_13") (pintype "passive"))
      (node (ref "MS5") (pin "11") (pinfunction "A1_11") (pintype "passive"))
      (node (ref "MS5") (pin "12") (pinfunction "A0_12") (pintype "passive"))
      (node (ref "MS5") (pin "13") (pinfunction "G_13") (pintype "passive"))
      (node (ref "MS6") (pin "11") (pinfunction "A1_11") (pintype "passive"))
      (node (ref "MS6") (pin "12") (pinfunction "A0_12") (pintype "passive"))
      (node (ref "MS6") (pin "13") (pinfunction "G_13") (pintype "passive"))
      (node (ref "MS7") (pin "11") (pinfunction "A1_11") (pintype "passive"))
      (node (ref "MS7") (pin "12") (pinfunction "A0_12") (pintype "passive"))
      (node (ref "MS7") (pin "13") (pinfunction "G_13") (pintype "passive"))
      (node (ref "MS8") (pin "11") (pinfunction "A1_11") (pintype "passive"))
      (node (ref "MS8") (pin "12") (pinfunction "A0_12") (pintype "passive"))
      (node (ref "MS8") (pin "13") (pinfunction "G_13") (pintype "passive"))
      (node (ref "P1-") (pin "1") (pinfunction "pad_1") (pintype "passive"))
      (node (ref "P2-") (pin "1") (pinfunction "pad_1") (pintype "passive"))
      (node (ref "R1") (pin "1") (pinfunction "1_1") (pintype "passive"))
      (node (ref "S1") (pin "2") (pinfunction "2_2") (pintype "passive"))
      (node (ref "S2") (pin "2") (pinfunction "2_2") (pintype "passive"))
      (node (ref "SW1") (pin "2") (pinfunction "2_2") (pintype "bidirectional"))
      (node (ref "SW1") (pin "4") (pinfunction "4_4") (pintype "bidirectional"))
      (node (ref "U1") (pin "2") (pinfunction "GND_2") (pintype "passive"))
      (node (ref "U2") (pin "2") (pinfunction "GND_2") (pintype "power_in"))
      (node (ref "U3") (pin "1") (pinfunction "GND_1") (pintype "power_in"))
      (node (ref "U3") (pin "12") (pinfunction "GND_12") (pintype "power_in"))
      (node (ref "U3") (pin "24") (pinfunction "GND_24") (pintype "power_in"))
      (node (ref "U3") (pin "39") (pinfunction "GND_39") (pintype "power_in"))
      (node (ref "U4") (pin "8") (pinfunction "GND_8") (pintype "passive"))
    )
    (net (code "80") (name "Net-(D1-K)") (class "Default")
      (node (ref "C1") (pin "2") (pinfunction "2_2") (pintype "passive"))
      (node (ref "D1") (pin "2") (pinfunction "K_2") (pintype "passive"))
      (node (ref "Q1") (pin "2") (pinfunction "S_2") (pintype "passive"))
      (node (ref "R2") (pin "2") (pinfunction "2_2") (pintype "passive"))
      (node (ref "U2") (pin "1") (pinfunction "VIN_1") (pintype "power_in"))
    )
    (net (code "81") (name "Net-(D2-A)") (class "Default")
      (node (ref "D2") (pin "1") (pinfunction "A_1") (pintype "passive"))
      (node (ref "R5") (pin "1") (pinfunction "1_1") (pintype "passive"))
      (node (ref "SW1") (pin "1") (pinfunction "1_1") (pintype "bidirectional"))
    )
    (net (code "82") (name "Net-(L1-Pad2)") (class "Default")
      (node (ref "L1") (pin "2") (pinfunction "2_2") (pintype "passive"))
      (node (ref "L2") (pin "1") (pinfunction "1_1") (pintype "passive"))
    )
    (net (code "83") (name "Net-(MCP1-~{RESET})") (class "Default")
      (node (ref "MCP1") (pin "18") (pinfunction "~{RESET}_18") (pintype "passive"))
      (node (ref "R6") (pin "2") (pinfunction "2_2") (pintype "passive"))
    )
    (net (code "84") (name "Net-(MCP2-A0)") (class "Default")
      (node (ref "MCP2") (pin "15") (pinfunction "A0_15") (pintype "passive"))
      (node (ref "R8") (pin "1") (pinfunction "1_1") (pintype "passive"))
    )
    (net (code "85") (name "Net-(MCP2-~{RESET})") (class "Default")
      (node (ref "MCP2") (pin "18") (pinfunction "~{RESET}_18") (pintype "passive"))
      (node (ref "R7") (pin "2") (pinfunction "2_2") (pintype "passive"))
    )
    (net (code "86") (name "Net-(MCP3-A2_1)") (class "Default")
      (node (ref "MCP3") (pin "16") (pinfunction "A2_1_16") (pintype "passive"))
      (node (ref "R10") (pin "1") (pinfunction "1_1") (pintype "passive"))
    )
    (net (code "87") (name "Net-(MCP3-~{RESET})") (class "Default")
      (node (ref "MCP3") (pin "18") (pinfunction "~{RESET}_18") (pintype "passive"))
      (node (ref "R9") (pin "2") (pinfunction "2_2") (pintype "passive"))
    )
    (net (code "88") (name "Net-(R11-Pad2)") (class "Default")
      (node (ref "R11") (pin "2") (pinfunction "2_2") (pintype "passive"))
      (node (ref "S1") (pin "1") (pinfunction "1_1") (pintype "passive"))
    )
    (net (code "89") (name "Net-(R12-Pad2)") (class "Default")
      (node (ref "R12") (pin "2") (pinfunction "2_2") (pintype "passive"))
      (node (ref "S2") (pin "1") (pinfunction "1_1") (pintype "passive"))
    )
    (net (code "90") (name "Net-(U2-EN)") (class "Default")
      (node (ref "R2") (pin "1") (pinfunction "1_1") (pintype "passive"))
      (node (ref "U2") (pin "3") (pinfunction "EN_3") (pintype "power_in"))
    )
    (net (code "91") (name "Net-(U3-DCC)") (class "Default")
      (node (ref "L1") (pin "1") (pinfunction "1_1") (pintype "passive"))
      (node (ref "U3") (pin "10") (pinfunction "DCC_10") (pintype "power_in"))
    )
    (net (code "92") (name "Net-(U3-DEC4)") (class "Default")
      (node (ref "C6") (pin "2") (pinfunction "2_2") (pintype "passive"))
      (node (ref "L2") (pin "2") (pinfunction "2_2") (pintype "passive"))
      (node (ref "U3") (pin "9") (pinfunction "DEC4_9") (pintype "power_in"))
    )
    (net (code "93") (name "Net-(U3-P0.00{slash}XL1)") (class "Default")
      (node (ref "C3") (pin "1") (pinfunction "1_1") (pintype "passive"))
      (node (ref "U3") (pin "13") (pinfunction "P0.00/XL1_13") (pintype "bidirectional"))
      (node (ref "X1") (pin "2") (pinfunction "OSC2_2") (pintype "passive"))
    )
    (net (code "94") (name "Net-(U3-P0.01{slash}XL2)") (class "Default")
      (node (ref "C4") (pin "1") (pinfunction "1_1") (pintype "passive"))
      (node (ref "U3") (pin "14") (pinfunction "P0.01/XL2_14") (pintype "bidirectional"))
      (node (ref "X1") (pin "1") (pinfunction "OSC1_1") (pintype "passive"))
    )
    (net (code "95") (name "VBAT") (class "Default")
      (node (ref "Q1") (pin "3") (pinfunction "D_3") (pintype "passive"))
      (node (ref "U1") (pin "1") (pinfunction "VBAT_1") (pintype "passive"))
    )
    (net (code "96") (name "VBUSIN") (class "Default")
      (node (ref "D1") (pin "1") (pinfunction "A_1") (pintype "passive"))
      (node (ref "Q1") (pin "1") (pinfunction "G_1") (pintype "passive"))
      (node (ref "R1") (pin "2") (pinfunction "2_2") (pintype "passive"))
      (node (ref "U4") (pin "7") (pinfunction "VBUSIN_7") (pintype "passive"))
    )
    (net (code "97") (name "VIN") (class "Default")
      (node (ref "DSK1") (pin "1") (pinfunction "K_1") (pintype "passive"))
      (node (ref "DSK2") (pin "1") (pinfunction "K_1") (pintype "passive"))
      (node (ref "S1") (pin "3") (pinfunction "3_3") (pintype "passive"))
      (node (ref "S2") (pin "3") (pinfunction "3_3") (pintype "passive"))
    )
    (net (code "98") (name "VIN1") (class "Default")
      (node (ref "P1+") (pin "1") (pinfunction "pad_1") (pintype "passive"))
      (node (ref "S1") (pin "4") (pinfunction "4_4") (pintype "passive"))
    )
    (net (code "99") (name "VIN2") (class "Default")
      (node (ref "P2+") (pin "1") (pinfunction "pad_1") (pintype "passive"))
      (node (ref "S2") (pin "4") (pinfunction "4_4") (pintype "passive"))
    )
    (net (code "100") (name "unconnected-(MCP1-INTA-Pad20)") (class "Default")
      (node (ref "MCP1") (pin "20") (pinfunction "INTA_20") (pintype "passive"))
    )
    (net (code "101") (name "unconnected-(MCP1-INTB-Pad19)") (class "Default")
      (node (ref "MCP1") (pin "19") (pinfunction "INTB_19") (pintype "passive"))
    )
    (net (code "102") (name "unconnected-(MCP1-NC_1-Pad11)") (class "Default")
      (node (ref "MCP1") (pin "11") (pinfunction "NC_1_11") (pintype "passive"))
    )
    (net (code "103") (name "unconnected-(MCP1-NC_2-Pad14)") (class "Default")
      (node (ref "MCP1") (pin "14") (pinfunction "NC_2_14") (pintype "passive"))
    )
    (net (code "104") (name "unconnected-(MCP2-INTA-Pad20)") (class "Default")
      (node (ref "MCP2") (pin "20") (pinfunction "INTA_20") (pintype "passive"))
    )
    (net (code "105") (name "unconnected-(MCP2-INTB-Pad19)") (class "Default")
      (node (ref "MCP2") (pin "19") (pinfunction "INTB_19") (pintype "passive"))
    )
    (net (code "106") (name "unconnected-(MCP2-NC_1-Pad11)") (class "Default")
      (node (ref "MCP2") (pin "11") (pinfunction "NC_1_11") (pintype "passive"))
    )
    (net (code "107") (name "unconnected-(MCP2-NC_2-Pad14)") (class "Default")
      (node (ref "MCP2") (pin "14") (pinfunction "NC_2_14") (pintype "passive"))
    )
    (net (code "108") (name "unconnected-(MCP3-GPA7-Pad28)") (class "Default")
      (node (ref "MCP3") (pin "28") (pinfunction "GPA7_28") (pintype "passive"))
    )
    (net (code "109") (name "unconnected-(MCP3-INTA-Pad20)") (class "Default")
      (node (ref "MCP3") (pin "20") (pinfunction "INTA_20") (pintype "passive"))
    )
    (net (code "110") (name "unconnected-(MCP3-INTB-Pad19)") (class "Default")
      (node (ref "MCP3") (pin "19") (pinfunction "INTB_19") (pintype "passive"))
    )
    (net (code "111") (name "unconnected-(MCP3-NC_1-Pad11)") (class "Default")
      (node (ref "MCP3") (pin "11") (pinfunction "NC_1_11") (pintype "passive"))
    )
    (net (code "112") (name "unconnected-(MCP3-NC_2-Pad14)") (class "Default")
      (node (ref "MCP3") (pin "14") (pinfunction "NC_2_14") (pintype "passive"))
    )
    (net (code "113") (name "unconnected-(MS1-INT-Pad1)") (class "Default")
      (node (ref "MS1") (pin "1") (pinfunction "INT_1") (pintype "passive"))
    )
    (net (code "114") (name "unconnected-(MS1-Pad4)") (class "Default")
      (node (ref "MS1") (pin "4") (pintype "passive"))
    )
    (net (code "115") (name "unconnected-(MS1-Pad9)") (class "Default")
      (node (ref "MS1") (pin "9") (pintype "passive"))
    )
    (net (code "116") (name "unconnected-(MS1-Pad10)") (class "Default")
      (node (ref "MS1") (pin "10") (pintype "passive"))
    )
    (net (code "117") (name "unconnected-(MS1-Pad14)") (class "Default")
      (node (ref "MS1") (pin "14") (pintype "passive"))
    )
    (net (code "118") (name "unconnected-(MS1-Pad16)") (class "Default")
      (node (ref "MS1") (pin "16") (pintype "passive"))
    )
    (net (code "119") (name "unconnected-(MS1-Pad17)") (class "Default")
      (node (ref "MS1") (pin "17") (pintype "passive"))
    )
    (net (code "120") (name "unconnected-(MS1-TRIG-Pad7)") (class "Default")
      (node (ref "MS1") (pin "7") (pinfunction "TRIG_7") (pintype "passive"))
    )
    (net (code "121") (name "unconnected-(MS2-INT-Pad1)") (class "Default")
      (node (ref "MS2") (pin "1") (pinfunction "INT_1") (pintype "passive"))
    )
    (net (code "122") (name "unconnected-(MS2-Pad4)") (class "Default")
      (node (ref "MS2") (pin "4") (pintype "passive"))
    )
    (net (code "123") (name "unconnected-(MS2-Pad9)") (class "Default")
      (node (ref "MS2") (pin "9") (pintype "passive"))
    )
    (net (code "124") (name "unconnected-(MS2-Pad10)") (class "Default")
      (node (ref "MS2") (pin "10") (pintype "passive"))
    )
    (net (code "125") (name "unconnected-(MS2-Pad14)") (class "Default")
      (node (ref "MS2") (pin "14") (pintype "passive"))
    )
    (net (code "126") (name "unconnected-(MS2-Pad16)") (class "Default")
      (node (ref "MS2") (pin "16") (pintype "passive"))
    )
    (net (code "127") (name "unconnected-(MS2-Pad17)") (class "Default")
      (node (ref "MS2") (pin "17") (pintype "passive"))
    )
    (net (code "128") (name "unconnected-(MS2-TRIG-Pad7)") (class "Default")
      (node (ref "MS2") (pin "7") (pinfunction "TRIG_7") (pintype "passive"))
    )
    (net (code "129") (name "unconnected-(MS3-INT-Pad1)") (class "Default")
      (node (ref "MS3") (pin "1") (pinfunction "INT_1") (pintype "passive"))
    )
    (net (code "130") (name "unconnected-(MS3-Pad4)") (class "Default")
      (node (ref "MS3") (pin "4") (pintype "passive"))
    )
    (net (code "131") (name "unconnected-(MS3-Pad9)") (class "Default")
      (node (ref "MS3") (pin "9") (pintype "passive"))
    )
    (net (code "132") (name "unconnected-(MS3-Pad10)") (class "Default")
      (node (ref "MS3") (pin "10") (pintype "passive"))
    )
    (net (code "133") (name "unconnected-(MS3-Pad14)") (class "Default")
      (node (ref "MS3") (pin "14") (pintype "passive"))
    )
    (net (code "134") (name "unconnected-(MS3-Pad16)") (class "Default")
      (node (ref "MS3") (pin "16") (pintype "passive"))
    )
    (net (code "135") (name "unconnected-(MS3-Pad17)") (class "Default")
      (node (ref "MS3") (pin "17") (pintype "passive"))
    )
    (net (code "136") (name "unconnected-(MS3-TRIG-Pad7)") (class "Default")
      (node (ref "MS3") (pin "7") (pinfunction "TRIG_7") (pintype "passive"))
    )
    (net (code "137") (name "unconnected-(MS4-INT-Pad1)") (class "Default")
      (node (ref "MS4") (pin "1") (pinfunction "INT_1") (pintype "passive"))
    )
    (net (code "138") (name "unconnected-(MS4-Pad4)") (class "Default")
      (node (ref "MS4") (pin "4") (pintype "passive"))
    )
    (net (code "139") (name "unconnected-(MS4-Pad9)") (class "Default")
      (node (ref "MS4") (pin "9") (pintype "passive"))
    )
    (net (code "140") (name "unconnected-(MS4-Pad10)") (class "Default")
      (node (ref "MS4") (pin "10") (pintype "passive"))
    )
    (net (code "141") (name "unconnected-(MS4-Pad14)") (class "Default")
      (node (ref "MS4") (pin "14") (pintype "passive"))
    )
    (net (code "142") (name "unconnected-(MS4-Pad16)") (class "Default")
      (node (ref "MS4") (pin "16") (pintype "passive"))
    )
    (net (code "143") (name "unconnected-(MS4-Pad17)") (class "Default")
      (node (ref "MS4") (pin "17") (pintype "passive"))
    )
    (net (code "144") (name "unconnected-(MS4-TRIG-Pad7)") (class "Default")
      (node (ref "MS4") (pin "7") (pinfunction "TRIG_7") (pintype "passive"))
    )
    (net (code "145") (name "unconnected-(MS5-INT-Pad1)") (class "Default")
      (node (ref "MS5") (pin "1") (pinfunction "INT_1") (pintype "passive"))
    )
    (net (code "146") (name "unconnected-(MS5-Pad4)") (class "Default")
      (node (ref "MS5") (pin "4") (pintype "passive"))
    )
    (net (code "147") (name "unconnected-(MS5-Pad9)") (class "Default")
      (node (ref "MS5") (pin "9") (pintype "passive"))
    )
    (net (code "148") (name "unconnected-(MS5-Pad10)") (class "Default")
      (node (ref "MS5") (pin "10") (pintype "passive"))
    )
    (net (code "149") (name "unconnected-(MS5-Pad14)") (class "Default")
      (node (ref "MS5") (pin "14") (pintype "passive"))
    )
    (net (code "150") (name "unconnected-(MS5-Pad16)") (class "Default")
      (node (ref "MS5") (pin "16") (pintype "passive"))
    )
    (net (code "151") (name "unconnected-(MS5-Pad17)") (class "Default")
      (node (ref "MS5") (pin "17") (pintype "passive"))
    )
    (net (code "152") (name "unconnected-(MS5-TRIG-Pad7)") (class "Default")
      (node (ref "MS5") (pin "7") (pinfunction "TRIG_7") (pintype "passive"))
    )
    (net (code "153") (name "unconnected-(MS6-INT-Pad1)") (class "Default")
      (node (ref "MS6") (pin "1") (pinfunction "INT_1") (pintype "passive"))
    )
    (net (code "154") (name "unconnected-(MS6-Pad4)") (class "Default")
      (node (ref "MS6") (pin "4") (pintype "passive"))
    )
    (net (code "155") (name "unconnected-(MS6-Pad9)") (class "Default")
      (node (ref "MS6") (pin "9") (pintype "passive"))
    )
    (net (code "156") (name "unconnected-(MS6-Pad10)") (class "Default")
      (node (ref "MS6") (pin "10") (pintype "passive"))
    )
    (net (code "157") (name "unconnected-(MS6-Pad14)") (class "Default")
      (node (ref "MS6") (pin "14") (pintype "passive"))
    )
    (net (code "158") (name "unconnected-(MS6-Pad16)") (class "Default")
      (node (ref "MS6") (pin "16") (pintype "passive"))
    )
    (net (code "159") (name "unconnected-(MS6-Pad17)") (class "Default")
      (node (ref "MS6") (pin "17") (pintype "passive"))
    )
    (net (code "160") (name "unconnected-(MS6-TRIG-Pad7)") (class "Default")
      (node (ref "MS6") (pin "7") (pinfunction "TRIG_7") (pintype "passive"))
    )
    (net (code "161") (name "unconnected-(MS7-INT-Pad1)") (class "Default")
      (node (ref "MS7") (pin "1") (pinfunction "INT_1") (pintype "passive"))
    )
    (net (code "162") (name "unconnected-(MS7-Pad4)") (class "Default")
      (node (ref "MS7") (pin "4") (pintype "passive"))
    )
    (net (code "163") (name "unconnected-(MS7-Pad9)") (class "Default")
      (node (ref "MS7") (pin "9") (pintype "passive"))
    )
    (net (code "164") (name "unconnected-(MS7-Pad10)") (class "Default")
      (node (ref "MS7") (pin "10") (pintype "passive"))
    )
    (net (code "165") (name "unconnected-(MS7-Pad14)") (class "Default")
      (node (ref "MS7") (pin "14") (pintype "passive"))
    )
    (net (code "166") (name "unconnected-(MS7-Pad16)") (class "Default")
      (node (ref "MS7") (pin "16") (pintype "passive"))
    )
    (net (code "167") (name "unconnected-(MS7-Pad17)") (class "Default")
      (node (ref "MS7") (pin "17") (pintype "passive"))
    )
    (net (code "168") (name "unconnected-(MS7-TRIG-Pad7)") (class "Default")
      (node (ref "MS7") (pin "7") (pinfunction "TRIG_7") (pintype "passive"))
    )
    (net (code "169") (name "unconnected-(MS8-INT-Pad1)") (class "Default")
      (node (ref "MS8") (pin "1") (pinfunction "INT_1") (pintype "passive"))
    )
    (net (code "170") (name "unconnected-(MS8-Pad4)") (class "Default")
      (node (ref "MS8") (pin "4") (pintype "passive"))
    )
    (net (code "171") (name "unconnected-(MS8-Pad9)") (class "Default")
      (node (ref "MS8") (pin "9") (pintype "passive"))
    )
    (net (code "172") (name "unconnected-(MS8-Pad10)") (class "Default")
      (node (ref "MS8") (pin "10") (pintype "passive"))
    )
    (net (code "173") (name "unconnected-(MS8-Pad14)") (class "Default")
      (node (ref "MS8") (pin "14") (pintype "passive"))
    )
    (net (code "174") (name "unconnected-(MS8-Pad16)") (class "Default")
      (node (ref "MS8") (pin "16") (pintype "passive"))
    )
    (net (code "175") (name "unconnected-(MS8-Pad17)") (class "Default")
      (node (ref "MS8") (pin "17") (pintype "passive"))
    )
    (net (code "176") (name "unconnected-(MS8-TRIG-Pad7)") (class "Default")
      (node (ref "MS8") (pin "7") (pinfunction "TRIG_7") (pintype "passive"))
    )
    (net (code "177") (name "unconnected-(SW1-Pad5)") (class "Default")
      (node (ref "SW1") (pin "5") (pinfunction "5_5") (pintype "bidirectional"))
    )
    (net (code "178") (name "unconnected-(U2-P4-Pad4)") (class "Default")
      (node (ref "U2") (pin "4") (pinfunction "P4_4") (pintype "power_in"))
    )
    (net (code "179") (name "unconnected-(U3-P0.20-Pad34)") (class "Default")
      (node (ref "U3") (pin "34") (pinfunction "P0.20_34") (pintype "bidirectional"))
    )
    (net (code "180") (name "unconnected-(U3-P0.22-Pad38)") (class "Default")
      (node (ref "U3") (pin "38") (pinfunction "P0.22_38") (pintype "bidirectional"))
    )
    (net (code "181") (name "unconnected-(U3-P0.23-Pad41)") (class "Default")
      (node (ref "U3") (pin "41") (pinfunction "P0.23_41") (pintype "bidirectional"))
    )
    (net (code "182") (name "unconnected-(U3-P0.24-Pad40)") (class "Default")
      (node (ref "U3") (pin "40") (pinfunction "P0.24_40") (pintype "bidirectional"))
    )
    (net (code "183") (name "unconnected-(U3-P0.29-Pad6)") (class "Default")
      (node (ref "U3") (pin "6") (pinfunction "P0.29_6") (pintype "bidirectional"))
    )
    (net (code "184") (name "unconnected-(U3-P0.30-Pad7)") (class "Default")
      (node (ref "U3") (pin "7") (pinfunction "P0.30_7") (pintype "bidirectional"))
    )
    (net (code "185") (name "unconnected-(U3-P0.31-Pad8)") (class "Default")
      (node (ref "U3") (pin "8") (pinfunction "P0.31_8") (pintype "bidirectional"))
    )
  )
)
